# Main_Board.net
KiCad netlist of a schematic drawn in Altium Designer
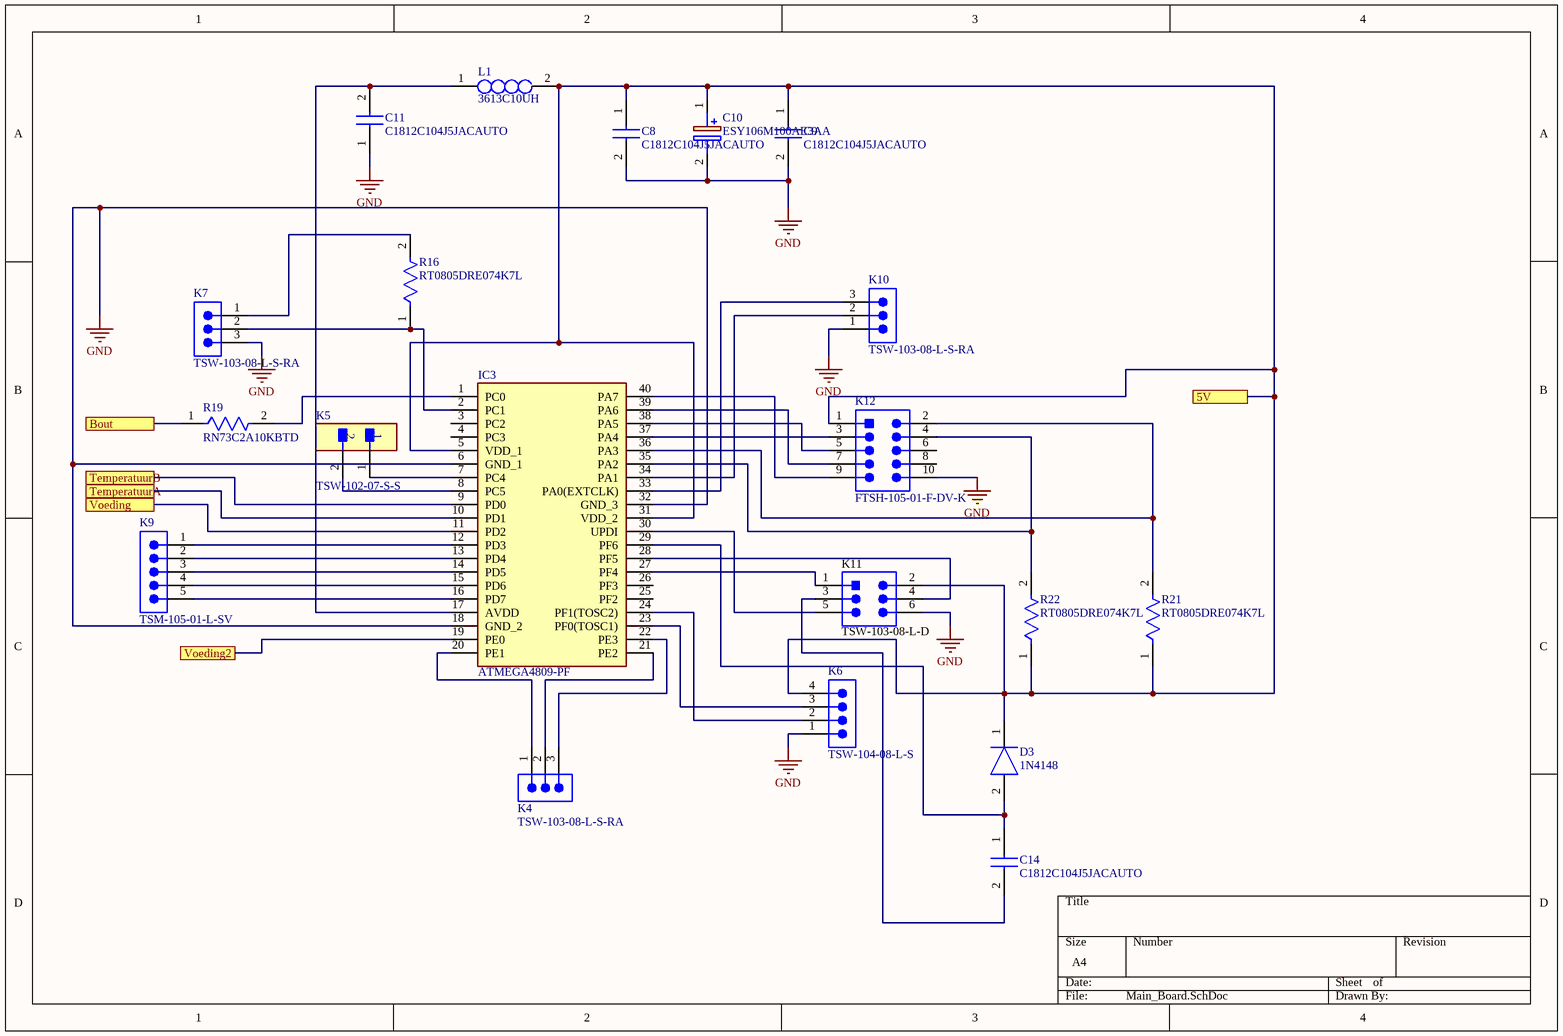
[diagram p0: Main_Board.SchDoc]

(export (version "E")
  (design (tool "Eeschema 10.0.6"))
  (components
    (comp (ref "C8")
      (value "C1812C104J5JACAUTO")
      (footprint "SamacSys:CAPC4532X110N")
      (description "Capacitor")
      (libsource (lib "*") (part "C1812C104J5JACAUTO"))
    )
    (comp (ref "C9")
      (value "C1812C104J5JACAUTO")
      (footprint "SamacSys:CAPC4532X110N")
      (description "Capacitor")
      (libsource (lib "*") (part "C1812C104J5JACAUTO"))
    )
    (comp (ref "C10")
      (value "ESY106M100AE3AA")
      (footprint "SamacSys:CAPPRD250W50D630H1250")
      (description "Capacitor Polarised")
      (libsource (lib "*") (part "ESY106M100AE3AA"))
    )
    (comp (ref "C11")
      (value "C1812C104J5JACAUTO")
      (footprint "SamacSys:CAPC4532X110N")
      (description "Capacitor")
      (libsource (lib "*") (part "C1812C104J5JACAUTO"))
    )
    (comp (ref "C14")
      (value "C1812C104J5JACAUTO")
      (footprint "SamacSys:CAPC4532X110N")
      (description "Capacitor")
      (libsource (lib "*") (part "C1812C104J5JACAUTO"))
    )
    (comp (ref "D3")
      (value "1N4148")
      (footprint "SamacSys:DIOAD1165W56L425D185")
      (description "Diode")
      (libsource (lib "*") (part "1N4148"))
    )
    (comp (ref "IC3")
      (value "ATMEGA4809-PF")
      (footprint "SamacSys:DIP1543W58P254L5175H635Q40N")
      (description "Integrated Circuit")
      (fields (field (name "MOUSER2 PART NUMBER") "556-ATMEGA4809-PF"))
      (libsource (lib "*") (part "ATMEGA4809-PF"))
    )
    (comp (ref "K4")
      (value "TSW-103-08-L-S-RA")
      (footprint "SMTC-TSW-103-08-X-S-RA")
      (fields (field (name "MANUFACTURER") "Samtec"))
      (libsource (lib "Altium Content Vault") (part "SMTC-TSW-103-X-X-S-X"))
    )
    (comp (ref "K5")
      (value "TSW-102-07-S-S")
      (footprint "FP-TSW-102-07-S-S-MFG")
      (description "CONN HEADER VERT 2POS 2.54MM")
      (libsource (lib "Altium Content Vault") (part "3bc925449376181038e59eaffc5286c"))
    )
    (comp (ref "K6")
      (value "TSW-104-08-L-S")
      (footprint "SMTC-TSW-104-08-X-S")
      (description "0.025\" SQ Post Header, Through-hole, Vertical, -55 to 125 degC, 2.54 mm Pitch, 4-Pin, Male, RoHS")
      (fields (field (name "MANUFACTURER") "Samtec"))
      (libsource (lib "Altium Content Vault") (part "SMTC-TSW-104-08-X-S"))
    )
    (comp (ref "K7")
      (value "TSW-103-08-L-S-RA")
      (footprint "SMTC-TSW-103-08-X-S-RA")
      (fields (field (name "MANUFACTURER") "Samtec"))
      (libsource (lib "Altium Content Vault") (part "SMTC-TSW-103-X-X-S-X"))
    )
    (comp (ref "K9")
      (value "TSM-105-01-L-SV")
      (footprint "SMTC-TSM-105-01-X-SV")
      (description "0.025\" SQ Post Header, Surface Mount, Vertical, -55 to 125 degC, 2.54 mm Pitch, 5-Pin, Male, RoHS")
      (fields (field (name "MANUFACTURER") "Samtec"))
      (libsource (lib "Altium Content Vault") (part "SMTC-TSM-105-01-X-SV"))
    )
    (comp (ref "K10")
      (value "TSW-103-08-L-S-RA")
      (footprint "SMTC-TSW-103-08-X-S-RA")
      (fields (field (name "MANUFACTURER") "Samtec"))
      (libsource (lib "Altium Content Vault") (part "SMTC-TSW-103-X-X-S-X"))
    )
    (comp (ref "K11")
      (value "TSW-103-08-L-D")
      (footprint "SMTC-TSW-103-08-L-D_V")
      (fields (field (name "MANUFACTURER") "Samtec"))
      (libsource (lib "Altium Content Vault") (part "CN-2P-M-R6"))
    )
    (comp (ref "K12")
      (value "FTSH-105-01-F-DV-K")
      (footprint "SMTC-FTSH-105-01-L-DV-K_V")
      (description "Male Header, Pitch 1.27 mm, 2 x 5 Position, Height 6.12 mm, RoHS, Tube")
      (fields (field (name "MANUFACTURER") "Samtec"))
      (libsource (lib "Altium Content Vault") (part "CN-2P-M-R10"))
    )
    (comp (ref "L1")
      (value "3613C10UH")
      (footprint "SamacSys:INDM4532X340N")
      (description "Inductor")
      (libsource (lib "*") (part "3613C10UH"))
    )
    (comp (ref "R16")
      (value "RT0805DRE074K7L")
      (footprint "FP-RT0805-MFG")
      (description "RES SMD 4.7K OHM 0.5% 1/8W 0805")
      (fields
        (field (name "OCTOPART") "https://octopart.com/rt0805dre074k7l-yageo-1242027")
        (field (name "TOLERANCE") "0.01")
      )
      (libsource (lib "Altium Content Vault") (part "1029c3af85768c4190bb7ad29bc67b5"))
    )
    (comp (ref "R19")
      (value "RN73C2A10KBTD")
      (footprint "FP-RN732A-MFG")
      (description "SMD Chip Resistor, Thin Film, 10KΩ, 100 V, 0805 [2012 Metric], 100 mW, 0.1%, RN73 Series")
      (fields
        (field (name "MANUFACTURER") "TE Connectivity")
        (field (name "OCTOPART") "https://octopart.com/rn73c2a10kbtd-te+connectivity-22737006")
      )
      (libsource (lib "Altium Content Vault") (part "1029c3af85768c4190bb7ad29bc67b5"))
    )
    (comp (ref "R21")
      (value "RT0805DRE074K7L")
      (footprint "FP-RT0805-MFG")
      (description "RES SMD 4.7K OHM 0.5% 1/8W 0805")
      (fields
        (field (name "OCTOPART") "https://octopart.com/rt0805dre074k7l-yageo-1242027")
        (field (name "TOLERANCE") "0.01")
      )
      (libsource (lib "Altium Content Vault") (part "1029c3af85768c4190bb7ad29bc67b5"))
    )
    (comp (ref "R22")
      (value "RT0805DRE074K7L")
      (footprint "FP-RT0805-MFG")
      (description "RES SMD 4.7K OHM 0.5% 1/8W 0805")
      (fields
        (field (name "OCTOPART") "https://octopart.com/rt0805dre074k7l-yageo-1242027")
        (field (name "TOLERANCE") "0.01")
      )
      (libsource (lib "Altium Content Vault") (part "1029c3af85768c4190bb7ad29bc67b5"))
    )
  )
  (nets
    (net (code "1") (name "/5V") (class "Default")
      (node (ref "C10") (pin "1") (pinfunction "+_1") (pintype "passive"))
      (node (ref "C8") (pin "1") (pinfunction "1_1") (pintype "passive"))
      (node (ref "C9") (pin "1") (pinfunction "1_1") (pintype "passive"))
      (node (ref "D3") (pin "1") (pinfunction "K_1") (pintype "passive"))
      (node (ref "IC3") (pin "31") (pinfunction "VDD_2_31") (pintype "passive"))
      (node (ref "IC3") (pin "5") (pinfunction "VDD_1_5") (pintype "passive"))
      (node (ref "K11") (pin "2") (pinfunction "2_2") (pintype "passive"))
      (node (ref "K12") (pin "1") (pinfunction "1_1") (pintype "passive"))
      (node (ref "K6") (pin "4") (pinfunction "4_4") (pintype "passive"))
      (node (ref "L1") (pin "2") (pinfunction "2_2") (pintype "passive"))
      (node (ref "R21") (pin "1") (pinfunction "1_1") (pintype "passive"))
      (node (ref "R22") (pin "1") (pinfunction "1_1") (pintype "passive"))
    )
    (net (code "2") (name "/Bout") (class "Default")
      (node (ref "R19") (pin "1") (pinfunction "1_1") (pintype "passive"))
    )
    (net (code "3") (name "/TemperatuurA") (class "Default")
      (node (ref "IC3") (pin "10") (pinfunction "PD1_10") (pintype "passive"))
    )
    (net (code "4") (name "/TemperatuurB") (class "Default")
      (node (ref "IC3") (pin "9") (pinfunction "PD0_9") (pintype "passive"))
    )
    (net (code "5") (name "/Voeding") (class "Default")
      (node (ref "IC3") (pin "11") (pinfunction "PD2_11") (pintype "passive"))
    )
    (net (code "6") (name "/Voeding2") (class "Default")
      (node (ref "IC3") (pin "19") (pinfunction "PE0_19") (pintype "passive"))
    )
    (net (code "7") (name "GND") (class "Default")
      (node (ref "C10") (pin "2") (pinfunction "-_2") (pintype "passive"))
      (node (ref "C11") (pin "1") (pinfunction "1_1") (pintype "passive"))
      (node (ref "C8") (pin "2") (pinfunction "2_2") (pintype "passive"))
      (node (ref "C9") (pin "2") (pinfunction "2_2") (pintype "passive"))
      (node (ref "IC3") (pin "18") (pinfunction "GND_2_18") (pintype "passive"))
      (node (ref "IC3") (pin "32") (pinfunction "GND_3_32") (pintype "passive"))
      (node (ref "IC3") (pin "6") (pinfunction "GND_1_6") (pintype "passive"))
      (node (ref "K10") (pin "1") (pinfunction "1_1") (pintype "passive"))
      (node (ref "K11") (pin "6") (pinfunction "6_6") (pintype "passive"))
      (node (ref "K12") (pin "10") (pinfunction "10_10") (pintype "passive"))
      (node (ref "K6") (pin "1") (pinfunction "1_1") (pintype "passive"))
      (node (ref "K7") (pin "3") (pinfunction "3_3") (pintype "passive"))
    )
    (net (code "8") (name "Net-(C14-Pad2)") (class "Default")
      (node (ref "C14") (pin "2") (pinfunction "2_2") (pintype "passive"))
      (node (ref "K11") (pin "3") (pinfunction "3_3") (pintype "passive"))
    )
    (net (code "9") (name "Net-(D3-A)") (class "Default")
      (node (ref "C14") (pin "1") (pinfunction "1_1") (pintype "passive"))
      (node (ref "D3") (pin "2") (pinfunction "A_2") (pintype "passive"))
      (node (ref "IC3") (pin "29") (pinfunction "PF6_29") (pintype "passive"))
    )
    (net (code "10") (name "Net-(IC3-AVDD)") (class "Default")
      (node (ref "C11") (pin "2") (pinfunction "2_2") (pintype "passive"))
      (node (ref "IC3") (pin "17") (pinfunction "AVDD_17") (pintype "passive"))
      (node (ref "L1") (pin "1") (pinfunction "1_1") (pintype "passive"))
    )
    (net (code "11") (name "Net-(IC3-PA0(EXTCLK))") (class "Default")
      (node (ref "IC3") (pin "33") (pinfunction "PA0(EXTCLK)_33") (pintype "passive"))
      (node (ref "K10") (pin "3") (pinfunction "3_3") (pintype "passive"))
    )
    (net (code "12") (name "Net-(IC3-PA1)") (class "Default")
      (node (ref "IC3") (pin "34") (pinfunction "PA1_34") (pintype "passive"))
      (node (ref "K10") (pin "2") (pinfunction "2_2") (pintype "passive"))
    )
    (net (code "13") (name "Net-(IC3-PA2)") (class "Default")
      (node (ref "IC3") (pin "35") (pinfunction "PA2_35") (pintype "passive"))
      (node (ref "K12") (pin "4") (pinfunction "4_4") (pintype "passive"))
      (node (ref "R22") (pin "2") (pinfunction "2_2") (pintype "passive"))
    )
    (net (code "14") (name "Net-(IC3-PA3)") (class "Default")
      (node (ref "IC3") (pin "36") (pinfunction "PA3_36") (pintype "passive"))
      (node (ref "K12") (pin "2") (pinfunction "2_2") (pintype "passive"))
      (node (ref "R21") (pin "2") (pinfunction "2_2") (pintype "passive"))
    )
    (net (code "15") (name "Net-(IC3-PA4)") (class "Default")
      (node (ref "IC3") (pin "37") (pinfunction "PA4_37") (pintype "passive"))
      (node (ref "K12") (pin "3") (pinfunction "3_3") (pintype "passive"))
    )
    (net (code "16") (name "Net-(IC3-PA5)") (class "Default")
      (node (ref "IC3") (pin "38") (pinfunction "PA5_38") (pintype "passive"))
      (node (ref "K12") (pin "5") (pinfunction "5_5") (pintype "passive"))
    )
    (net (code "17") (name "Net-(IC3-PA6)") (class "Default")
      (node (ref "IC3") (pin "39") (pinfunction "PA6_39") (pintype "passive"))
      (node (ref "K12") (pin "7") (pinfunction "7_7") (pintype "passive"))
    )
    (net (code "18") (name "Net-(IC3-PA7)") (class "Default")
      (node (ref "IC3") (pin "40") (pinfunction "PA7_40") (pintype "passive"))
      (node (ref "K12") (pin "9") (pinfunction "9_9") (pintype "passive"))
    )
    (net (code "19") (name "Net-(IC3-PC0)") (class "Default")
      (node (ref "IC3") (pin "1") (pinfunction "PC0_1") (pintype "passive"))
      (node (ref "R19") (pin "2") (pinfunction "2_2") (pintype "passive"))
    )
    (net (code "20") (name "Net-(IC3-PC1)") (class "Default")
      (node (ref "IC3") (pin "2") (pinfunction "PC1_2") (pintype "passive"))
      (node (ref "K7") (pin "2") (pinfunction "2_2") (pintype "passive"))
      (node (ref "R16") (pin "1") (pinfunction "1_1") (pintype "passive"))
    )
    (net (code "21") (name "Net-(IC3-PC4)") (class "Default")
      (node (ref "IC3") (pin "7") (pinfunction "PC4_7") (pintype "passive"))
      (node (ref "K5") (pin "1") (pinfunction "1_1") (pintype "passive"))
    )
    (net (code "22") (name "Net-(IC3-PC5)") (class "Default")
      (node (ref "IC3") (pin "8") (pinfunction "PC5_8") (pintype "passive"))
      (node (ref "K5") (pin "2") (pinfunction "2_2") (pintype "passive"))
    )
    (net (code "23") (name "Net-(IC3-PD3)") (class "Default")
      (node (ref "IC3") (pin "12") (pinfunction "PD3_12") (pintype "passive"))
      (node (ref "K9") (pin "1") (pinfunction "1_1") (pintype "passive"))
    )
    (net (code "24") (name "Net-(IC3-PD4)") (class "Default")
      (node (ref "IC3") (pin "13") (pinfunction "PD4_13") (pintype "passive"))
      (node (ref "K9") (pin "2") (pinfunction "2_2") (pintype "passive"))
    )
    (net (code "25") (name "Net-(IC3-PD5)") (class "Default")
      (node (ref "IC3") (pin "14") (pinfunction "PD5_14") (pintype "passive"))
      (node (ref "K9") (pin "3") (pinfunction "3_3") (pintype "passive"))
    )
    (net (code "26") (name "Net-(IC3-PD6)") (class "Default")
      (node (ref "IC3") (pin "15") (pinfunction "PD6_15") (pintype "passive"))
      (node (ref "K9") (pin "4") (pinfunction "4_4") (pintype "passive"))
    )
    (net (code "27") (name "Net-(IC3-PD7)") (class "Default")
      (node (ref "IC3") (pin "16") (pinfunction "PD7_16") (pintype "passive"))
      (node (ref "K9") (pin "5") (pinfunction "5_5") (pintype "passive"))
    )
    (net (code "28") (name "Net-(IC3-PE1)") (class "Default")
      (node (ref "IC3") (pin "20") (pinfunction "PE1_20") (pintype "passive"))
      (node (ref "K4") (pin "1") (pinfunction "1_1") (pintype "passive"))
    )
    (net (code "29") (name "Net-(IC3-PE2)") (class "Default")
      (node (ref "IC3") (pin "21") (pinfunction "PE2_21") (pintype "passive"))
      (node (ref "K4") (pin "2") (pinfunction "2_2") (pintype "passive"))
    )
    (net (code "30") (name "Net-(IC3-PE3)") (class "Default")
      (node (ref "IC3") (pin "22") (pinfunction "PE3_22") (pintype "passive"))
      (node (ref "K4") (pin "3") (pinfunction "3_3") (pintype "passive"))
    )
    (net (code "31") (name "Net-(IC3-PF0(TOSC1))") (class "Default")
      (node (ref "IC3") (pin "23") (pinfunction "PF0(TOSC1)_23") (pintype "passive"))
      (node (ref "K6") (pin "3") (pinfunction "3_3") (pintype "passive"))
    )
    (net (code "32") (name "Net-(IC3-PF1(TOSC2))") (class "Default")
      (node (ref "IC3") (pin "24") (pinfunction "PF1(TOSC2)_24") (pintype "passive"))
      (node (ref "K6") (pin "2") (pinfunction "2_2") (pintype "passive"))
    )
    (net (code "33") (name "Net-(IC3-PF4)") (class "Default")
      (node (ref "IC3") (pin "27") (pinfunction "PF4_27") (pintype "passive"))
      (node (ref "K11") (pin "1") (pinfunction "1_1") (pintype "passive"))
    )
    (net (code "34") (name "Net-(IC3-PF5)") (class "Default")
      (node (ref "IC3") (pin "28") (pinfunction "PF5_28") (pintype "passive"))
      (node (ref "K11") (pin "4") (pinfunction "4_4") (pintype "passive"))
    )
    (net (code "35") (name "Net-(IC3-UPDI)") (class "Default")
      (node (ref "IC3") (pin "30") (pinfunction "UPDI_30") (pintype "passive"))
      (node (ref "K11") (pin "5") (pinfunction "5_5") (pintype "passive"))
    )
    (net (code "36") (name "Net-(K7-Pad1)") (class "Default")
      (node (ref "K7") (pin "1") (pinfunction "1_1") (pintype "passive"))
      (node (ref "R16") (pin "2") (pinfunction "2_2") (pintype "passive"))
    )
    (net (code "37") (name "unconnected-(IC3-PC2-Pad3)") (class "Default")
      (node (ref "IC3") (pin "3") (pinfunction "PC2_3") (pintype "passive"))
    )
    (net (code "38") (name "unconnected-(IC3-PC3-Pad4)") (class "Default")
      (node (ref "IC3") (pin "4") (pinfunction "PC3_4") (pintype "passive"))
    )
    (net (code "39") (name "unconnected-(IC3-PF2-Pad25)") (class "Default")
      (node (ref "IC3") (pin "25") (pinfunction "PF2_25") (pintype "passive"))
    )
    (net (code "40") (name "unconnected-(IC3-PF3-Pad26)") (class "Default")
      (node (ref "IC3") (pin "26") (pinfunction "PF3_26") (pintype "passive"))
    )
    (net (code "41") (name "unconnected-(K12-Pad6)") (class "Default")
      (node (ref "K12") (pin "6") (pinfunction "6_6") (pintype "passive"))
    )
    (net (code "42") (name "unconnected-(K12-Pad8)") (class "Default")
      (node (ref "K12") (pin "8") (pinfunction "8_8") (pintype "passive"))
    )
  )
)
